# ICeePotTransmitter.net
KiCad netlist of a schematic drawn in EAGLE
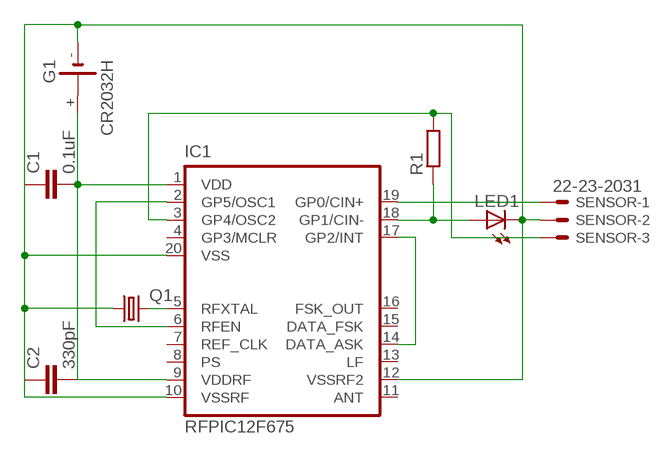
[diagram p0: schematic, sheet 1]

(export (version "E")
  (design (tool "Eeschema 10.0.6"))
  (components
    (comp (ref "C1")
      (value "0.1uF")
      (footprint "eagle-import:C0603K")
      (libsource (lib "eagle-import") (part "C-EUC0603K"))
    )
    (comp (ref "C2")
      (value "330pF")
      (footprint "eagle-import:C0603K")
      (libsource (lib "eagle-import") (part "C-EUC0603K"))
    )
    (comp (ref "G1")
      (value "CR2032H")
      (footprint "eagle-import:CR2032H")
      (libsource (lib "eagle-import") (part "CR2032H"))
    )
    (comp (ref "IC1")
      (value "RFPIC12F675")
      (footprint "eagle-import:SOIC20")
      (libsource (lib "eagle-import") (part "RFPIC12F675"))
    )
    (comp (ref "LED1")
      (value "LED5MM")
      (footprint "eagle-import:LED5MM")
      (libsource (lib "eagle-import") (part "LED5MM"))
    )
    (comp (ref "Q1")
      (value "CRYSTALHC49S")
      (footprint "eagle-import:HC49_S")
      (libsource (lib "eagle-import") (part "CRYSTALHC49S"))
    )
    (comp (ref "R1")
      (value "R-EU_0204/7")
      (footprint "eagle-import:0204_7")
      (libsource (lib "eagle-import") (part "R-EU_0204/7"))
    )
    (comp (ref "SENSOR")
      (value "22-23-2031")
      (footprint "eagle-import:22-23-2031")
      (fields (field (name "MF") "MOLEX"))
      (libsource (lib "eagle-import") (part "22-23-2031"))
    )
  )
  (nets
    (net (code "1") (name "Net-(IC1-DATA_ASK)") (class "Default")
      (node (ref "IC1") (pin "14") (pinfunction "DATA_ASK_14") (pintype "input"))
      (node (ref "IC1") (pin "17") (pinfunction "GP2/INT_17") (pintype "bidirectional"))
    )
    (net (code "2") (name "Net-(IC1-GP0{slash}CIN+)") (class "Default")
      (node (ref "IC1") (pin "19") (pinfunction "GP0/CIN+_19") (pintype "bidirectional"))
      (node (ref "SENSOR") (pin "1") (pinfunction "S_1") (pintype "passive"))
    )
    (net (code "3") (name "Net-(IC1-GP1{slash}CIN-)") (class "Default")
      (node (ref "IC1") (pin "18") (pinfunction "GP1/CIN-_18") (pintype "bidirectional"))
      (node (ref "LED1") (pin "A") (pinfunction "A_A") (pintype "passive"))
      (node (ref "R1") (pin "1") (pinfunction "1_1") (pintype "passive"))
    )
    (net (code "4") (name "Net-(IC1-GP4{slash}OSC2)") (class "Default")
      (node (ref "IC1") (pin "3") (pinfunction "GP4/OSC2_3") (pintype "bidirectional"))
      (node (ref "R1") (pin "2") (pinfunction "2_2") (pintype "passive"))
      (node (ref "SENSOR") (pin "3") (pinfunction "S_3") (pintype "passive"))
    )
    (net (code "5") (name "Net-(IC1-GP5{slash}OSC1)") (class "Default")
      (node (ref "IC1") (pin "2") (pinfunction "GP5/OSC1_2") (pintype "bidirectional"))
      (node (ref "IC1") (pin "6") (pinfunction "RFEN_6") (pintype "input"))
    )
    (net (code "6") (name "Net-(IC1-RFXTAL)") (class "Default")
      (node (ref "IC1") (pin "5") (pinfunction "RFXTAL_5") (pintype "input"))
      (node (ref "Q1") (pin "2") (pinfunction "2_2") (pintype "passive"))
    )
    (net (code "7") (name "Net-(IC1-VDD)") (class "Default")
      (node (ref "C1") (pin "2") (pinfunction "2_2") (pintype "passive"))
      (node (ref "C2") (pin "2") (pinfunction "2_2") (pintype "passive"))
      (node (ref "G1") (pin "+") (pinfunction "+_+") (pintype "passive"))
      (node (ref "IC1") (pin "1") (pinfunction "VDD_1") (pintype "power_in"))
      (node (ref "IC1") (pin "9") (pinfunction "VDDRF_9") (pintype "power_in"))
    )
    (net (code "8") (name "Net-(IC1-VSS)") (class "Default")
      (node (ref "C1") (pin "1") (pinfunction "1_1") (pintype "passive"))
      (node (ref "C2") (pin "1") (pinfunction "1_1") (pintype "passive"))
      (node (ref "G1") (pin "-") (pinfunction "-_-") (pintype "passive"))
      (node (ref "IC1") (pin "10") (pinfunction "VSSRF_10") (pintype "power_in"))
      (node (ref "IC1") (pin "12") (pinfunction "VSSRF2_12") (pintype "power_in"))
      (node (ref "IC1") (pin "20") (pinfunction "VSS_20") (pintype "power_in"))
      (node (ref "LED1") (pin "K") (pinfunction "C_K") (pintype "passive"))
      (node (ref "Q1") (pin "1") (pinfunction "1_1") (pintype "passive"))
      (node (ref "SENSOR") (pin "2") (pinfunction "S_2") (pintype "passive"))
    )
    (net (code "9") (name "unconnected-(G1-+-Pad+@1)") (class "Default")
      (node (ref "G1") (pin "+@1") (pinfunction "+_+@1") (pintype "passive"))
    )
    (net (code "10") (name "unconnected-(IC1-ANT-Pad11)") (class "Default")
      (node (ref "IC1") (pin "11") (pinfunction "ANT_11") (pintype "output"))
    )
    (net (code "11") (name "unconnected-(IC1-DATA_FSK-Pad15)") (class "Default")
      (node (ref "IC1") (pin "15") (pinfunction "DATA_FSK_15") (pintype "input"))
    )
    (net (code "12") (name "unconnected-(IC1-FSK_OUT-Pad16)") (class "Default")
      (node (ref "IC1") (pin "16") (pinfunction "FSK_OUT_16") (pintype "output"))
    )
    (net (code "13") (name "unconnected-(IC1-GP3{slash}MCLR-Pad4)") (class "Default")
      (node (ref "IC1") (pin "4") (pinfunction "GP3/MCLR_4") (pintype "bidirectional"))
    )
    (net (code "14") (name "unconnected-(IC1-LF-Pad13)") (class "Default")
      (node (ref "IC1") (pin "13") (pinfunction "LF_13") (pintype "bidirectional"))
    )
    (net (code "15") (name "unconnected-(IC1-PS-Pad8)") (class "Default")
      (node (ref "IC1") (pin "8") (pinfunction "PS_8") (pintype "bidirectional"))
    )
    (net (code "16") (name "unconnected-(IC1-REF_CLK-Pad7)") (class "Default")
      (node (ref "IC1") (pin "7") (pinfunction "REF_CLK_7") (pintype "bidirectional"))
    )
  )
)
